# LoRa.net
KiCad netlist of a schematic drawn in Altium Designer
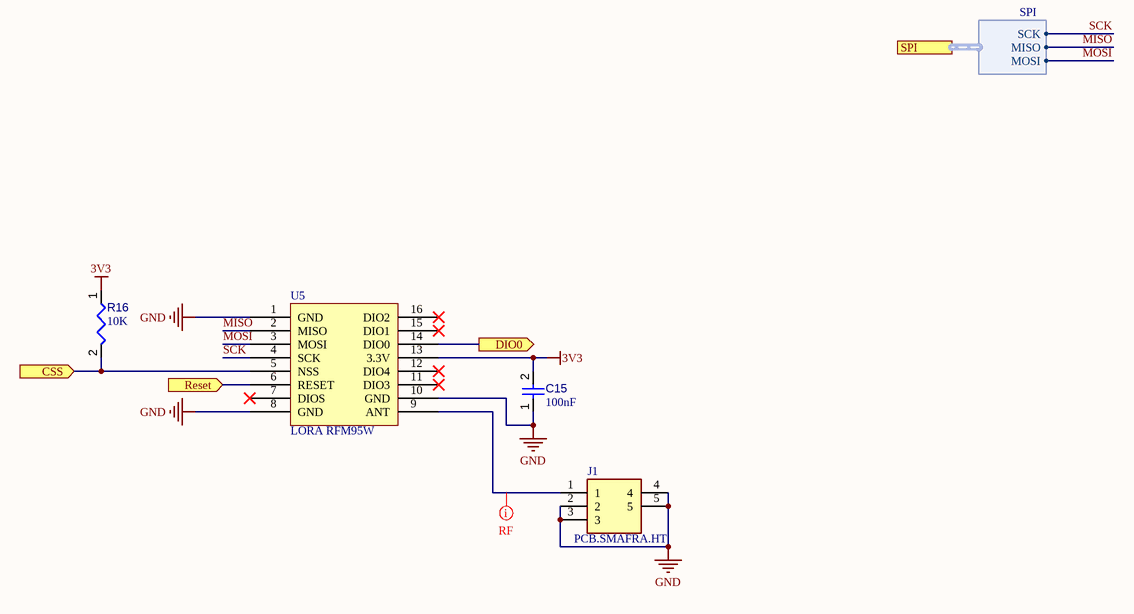
[diagram p0: LoRa.SchDoc]

(export (version "E")
  (design (tool "Eeschema 10.0.6"))
  (components
    (comp (ref "C15")
      (value "100nF")
      (footprint "CAPC0805(2012)145_L")
      (description "Chip Capacitor, 100µF +/-20%, 6.3V, 0805, Thickness 1.45 mm")
      (fields (field (name "TOLERANCE") "10%") (field (name "Comment") "Capacitor 100µF +/-20% 6.3V 0805"))
      (libsource (lib "PWr in Space team") (part "CAP-NP-2"))
    )
    (comp (ref "J1")
      (value "PCB.SMAFRA.HT")
      (footprint "PCBSMAFRAHT")
      (description "Connector")
      (fields (field (name "MOUSER PART NUMBER") "960-PCB.SMAFRA.HT"))
      (libsource (lib "PWr in Space team") (part "PCB.SMAFRA.HT"))
    )
    (comp (ref "R16")
      (value "10K")
      (footprint "RESC0805(2012)_L")
      (description "Chip Resistor, 4,7 Ohms, +/-5 %, 125 mW, -55 to 155 degC, 0805")
      (fields (field (name "TOLERANCE") "5%") (field (name "POWER") "125mW"))
      (libsource (lib "PWr in Space team") (part "RES-2"))
    )
    (comp (ref "U5")
      (value "LORA RFM95W")
      (footprint "LORA RFM95W - duplicate1")
      (libsource (lib "PWr in Space team") (part "LORA RFM95W"))
    )
  )
  (nets
    (net (code "2") (name "/CSS") (class "Default")
      (node (ref "R16") (pin "2") (pinfunction "2_2") (pintype "passive"))
      (node (ref "U5") (pin "5") (pinfunction "NSS_5") (pintype "passive"))
    )
    (net (code "3") (name "/DIO0") (class "Default")
      (node (ref "U5") (pin "14") (pinfunction "DIO0_14") (pintype "passive"))
    )
    (net (code "4") (name "/MISO") (class "Default")
      (node (ref "U5") (pin "2") (pinfunction "MISO_2") (pintype "passive"))
    )
    (net (code "5") (name "/MOSI") (class "Default")
      (node (ref "U5") (pin "3") (pinfunction "MOSI_3") (pintype "passive"))
    )
    (net (code "6") (name "/Reset") (class "Default")
      (node (ref "U5") (pin "6") (pinfunction "RESET_6") (pintype "passive"))
    )
    (net (code "7") (name "/SCK") (class "Default")
      (node (ref "U5") (pin "4") (pinfunction "SCK_4") (pintype "passive"))
    )
    (net (code "9") (name "3V3") (class "Default")
      (node (ref "C15") (pin "2") (pinfunction "2_2") (pintype "passive"))
      (node (ref "R16") (pin "1") (pinfunction "1_1") (pintype "passive"))
      (node (ref "U5") (pin "13") (pinfunction "3.3V_13") (pintype "passive"))
    )
    (net (code "10") (name "GND") (class "Default")
      (node (ref "C15") (pin "1") (pinfunction "1_1") (pintype "passive"))
      (node (ref "J1") (pin "2") (pinfunction "2_2") (pintype "passive"))
      (node (ref "J1") (pin "3") (pinfunction "3_3") (pintype "passive"))
      (node (ref "J1") (pin "4") (pinfunction "4_4") (pintype "passive"))
      (node (ref "J1") (pin "5") (pinfunction "5_5") (pintype "passive"))
      (node (ref "U5") (pin "1") (pinfunction "GND_1") (pintype "passive"))
      (node (ref "U5") (pin "10") (pinfunction "GND_10") (pintype "passive"))
      (node (ref "U5") (pin "8") (pinfunction "GND_8") (pintype "passive"))
    )
    (net (code "11") (name "Net-(U5-ANT)") (class "Default")
      (node (ref "J1") (pin "1") (pinfunction "1_1") (pintype "passive"))
      (node (ref "U5") (pin "9") (pinfunction "ANT_9") (pintype "passive"))
    )
    (net (code "12") (name "unconnected-(U5-DIO1-Pad15)") (class "Default")
      (node (ref "U5") (pin "15") (pinfunction "DIO1_15") (pintype "passive+no_connect"))
    )
    (net (code "13") (name "unconnected-(U5-DIO2-Pad16)") (class "Default")
      (node (ref "U5") (pin "16") (pinfunction "DIO2_16") (pintype "passive+no_connect"))
    )
    (net (code "14") (name "unconnected-(U5-DIO3-Pad11)") (class "Default")
      (node (ref "U5") (pin "11") (pinfunction "DIO3_11") (pintype "passive+no_connect"))
    )
    (net (code "15") (name "unconnected-(U5-DIO4-Pad12)") (class "Default")
      (node (ref "U5") (pin "12") (pinfunction "DIO4_12") (pintype "passive+no_connect"))
    )
    (net (code "16") (name "unconnected-(U5-DIOS-Pad7)") (class "Default")
      (node (ref "U5") (pin "7") (pinfunction "DIOS_7") (pintype "passive+no_connect"))
    )
  )
)
